# IN_V.net
KiCad netlist of a schematic drawn in Altium Designer
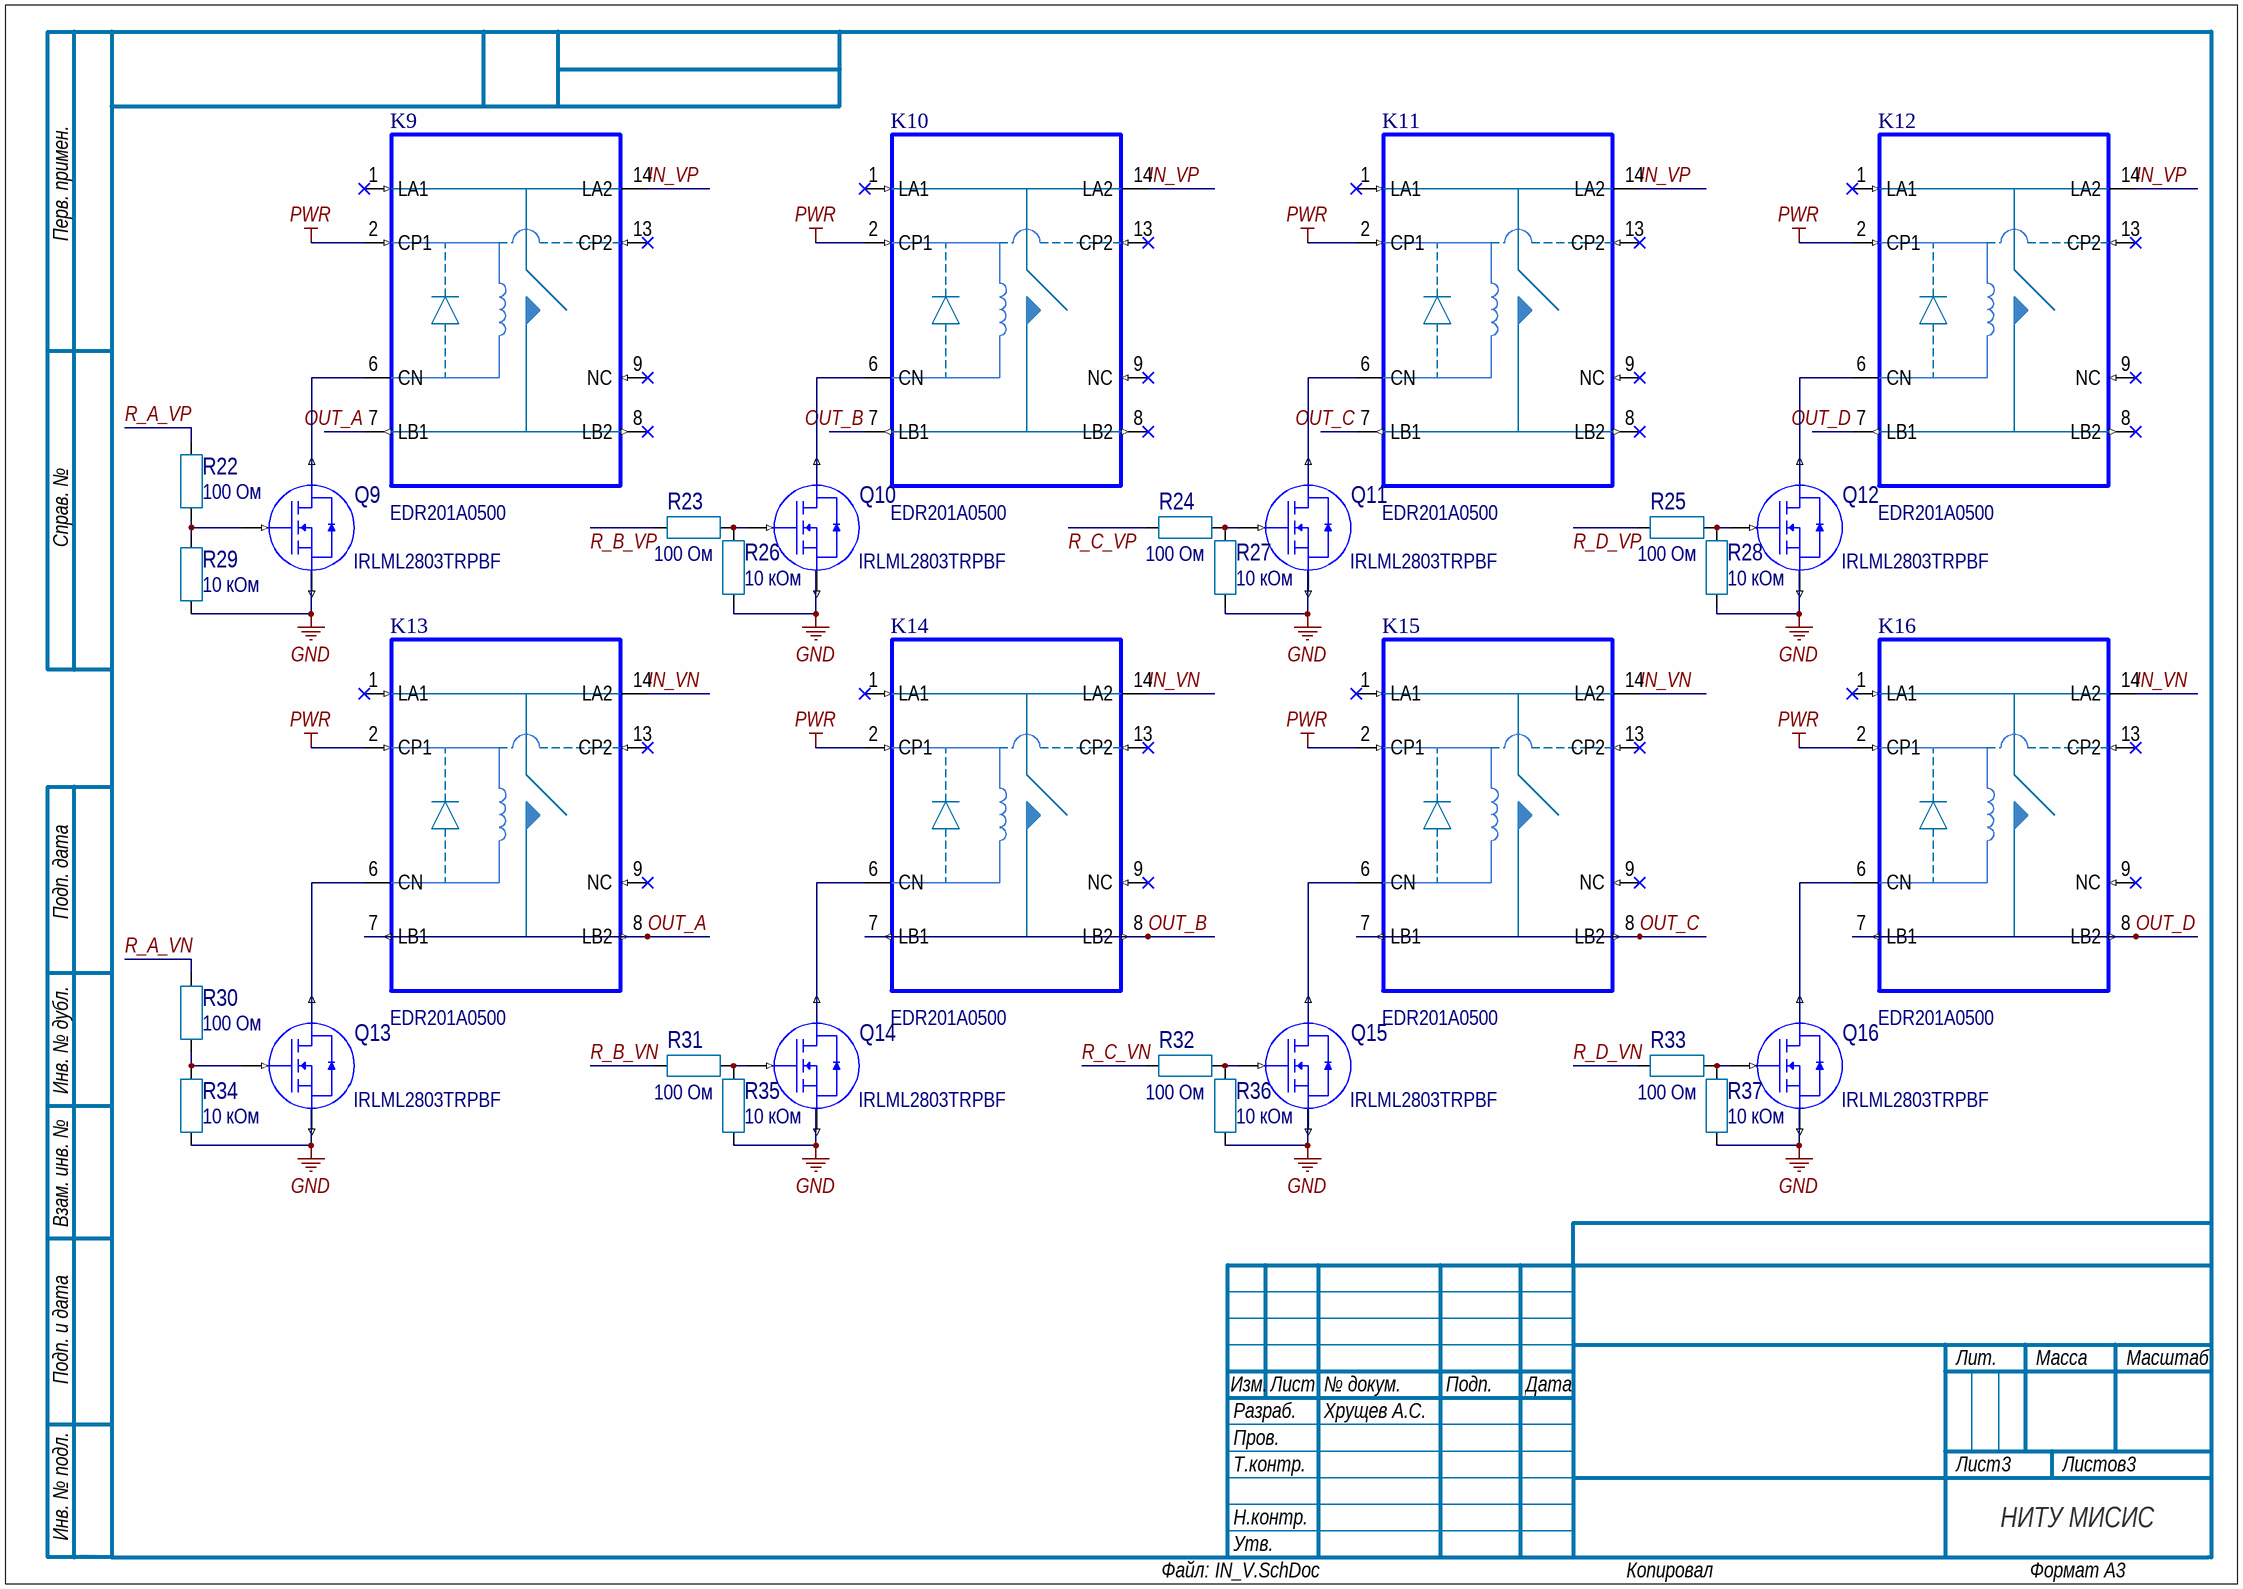
[diagram p0: IN_V.SchDoc]

(export (version "E")
  (design (tool "Eeschema 10.0.6"))
  (components
    (comp (ref "K9")
      (value "EDR201A0500")
      (footprint "DIP14")
      (description "Реле герконовое 5V / 1A,100V")
      (fields (field (name "MF") "Fairchild Semiconductor") (field (name "MP") "MM74HC32N"))
      (libsource (lib "EDR201A0500") (part "EDR201A0500"))
    )
    (comp (ref "K10")
      (value "EDR201A0500")
      (footprint "DIP14")
      (description "Реле герконовое 5V / 1A,100V")
      (fields (field (name "MF") "Fairchild Semiconductor") (field (name "MP") "MM74HC32N"))
      (libsource (lib "EDR201A0500") (part "EDR201A0500"))
    )
    (comp (ref "K11")
      (value "EDR201A0500")
      (footprint "DIP14")
      (description "Реле герконовое 5V / 1A,100V")
      (fields (field (name "MF") "Fairchild Semiconductor") (field (name "MP") "MM74HC32N"))
      (libsource (lib "EDR201A0500") (part "EDR201A0500"))
    )
    (comp (ref "K12")
      (value "EDR201A0500")
      (footprint "DIP14")
      (description "Реле герконовое 5V / 1A,100V")
      (fields (field (name "MF") "Fairchild Semiconductor") (field (name "MP") "MM74HC32N"))
      (libsource (lib "EDR201A0500") (part "EDR201A0500"))
    )
    (comp (ref "K13")
      (value "EDR201A0500")
      (footprint "DIP14")
      (description "Реле герконовое 5V / 1A,100V")
      (fields (field (name "MF") "Fairchild Semiconductor") (field (name "MP") "MM74HC32N"))
      (libsource (lib "EDR201A0500") (part "EDR201A0500"))
    )
    (comp (ref "K14")
      (value "EDR201A0500")
      (footprint "DIP14")
      (description "Реле герконовое 5V / 1A,100V")
      (fields (field (name "MF") "Fairchild Semiconductor") (field (name "MP") "MM74HC32N"))
      (libsource (lib "EDR201A0500") (part "EDR201A0500"))
    )
    (comp (ref "K15")
      (value "EDR201A0500")
      (footprint "DIP14")
      (description "Реле герконовое 5V / 1A,100V")
      (fields (field (name "MF") "Fairchild Semiconductor") (field (name "MP") "MM74HC32N"))
      (libsource (lib "EDR201A0500") (part "EDR201A0500"))
    )
    (comp (ref "K16")
      (value "EDR201A0500")
      (footprint "DIP14")
      (description "Реле герконовое 5V / 1A,100V")
      (fields (field (name "MF") "Fairchild Semiconductor") (field (name "MP") "MM74HC32N"))
      (libsource (lib "EDR201A0500") (part "EDR201A0500"))
    )
    (comp (ref "Q9")
      (value "IRLML2803TRPBF")
      (footprint "SOT23-3")
      (description "N-MOSFET 30V 1.2A SOT23")
      (libsource (lib "symbols") (part "IRLML2803TRPBF"))
    )
    (comp (ref "Q10")
      (value "IRLML2803TRPBF")
      (footprint "SOT23-3")
      (description "N-MOSFET 30V 1.2A SOT23")
      (libsource (lib "symbols") (part "IRLML2803TRPBF"))
    )
    (comp (ref "Q11")
      (value "IRLML2803TRPBF")
      (footprint "SOT23-3")
      (description "N-MOSFET 30V 1.2A SOT23")
      (libsource (lib "symbols") (part "IRLML2803TRPBF"))
    )
    (comp (ref "Q12")
      (value "IRLML2803TRPBF")
      (footprint "SOT23-3")
      (description "N-MOSFET 30V 1.2A SOT23")
      (libsource (lib "symbols") (part "IRLML2803TRPBF"))
    )
    (comp (ref "Q13")
      (value "IRLML2803TRPBF")
      (footprint "SOT23-3")
      (description "N-MOSFET 30V 1.2A SOT23")
      (libsource (lib "symbols") (part "IRLML2803TRPBF"))
    )
    (comp (ref "Q14")
      (value "IRLML2803TRPBF")
      (footprint "SOT23-3")
      (description "N-MOSFET 30V 1.2A SOT23")
      (libsource (lib "symbols") (part "IRLML2803TRPBF"))
    )
    (comp (ref "Q15")
      (value "IRLML2803TRPBF")
      (footprint "SOT23-3")
      (description "N-MOSFET 30V 1.2A SOT23")
      (libsource (lib "symbols") (part "IRLML2803TRPBF"))
    )
    (comp (ref "Q16")
      (value "IRLML2803TRPBF")
      (footprint "SOT23-3")
      (description "N-MOSFET 30V 1.2A SOT23")
      (libsource (lib "symbols") (part "IRLML2803TRPBF"))
    )
    (comp (ref "R22")
      (value "100 Ом")
      (footprint "R0805")
      (description "Резистор 100 Ом")
      (libsource (lib "GOST_2.728_Rezistory&Kondensatory") (part "R1_POSTOYANNYJ"))
    )
    (comp (ref "R23")
      (value "100 Ом")
      (footprint "R0805")
      (description "Резистор 100 Ом")
      (libsource (lib "") (part "R1_POSTOYANNYJ_1"))
    )
    (comp (ref "R24")
      (value "100 Ом")
      (footprint "R0805")
      (description "Резистор 100 Ом")
      (libsource (lib "") (part "R1_POSTOYANNYJ_1"))
    )
    (comp (ref "R25")
      (value "100 Ом")
      (footprint "R0805")
      (description "Резистор 100 Ом")
      (libsource (lib "") (part "R1_POSTOYANNYJ_1"))
    )
    (comp (ref "R26")
      (value "10 кОм")
      (footprint "R0805")
      (description "Резистор 100 Ом")
      (libsource (lib "GOST_2.728_Rezistory&Kondensatory") (part "R1_POSTOYANNYJ"))
    )
    (comp (ref "R27")
      (value "10 кОм")
      (footprint "R0805")
      (description "Резистор 100 Ом")
      (libsource (lib "GOST_2.728_Rezistory&Kondensatory") (part "R1_POSTOYANNYJ"))
    )
    (comp (ref "R28")
      (value "10 кОм")
      (footprint "R0805")
      (description "Резистор 100 Ом")
      (libsource (lib "GOST_2.728_Rezistory&Kondensatory") (part "R1_POSTOYANNYJ"))
    )
    (comp (ref "R29")
      (value "10 кОм")
      (footprint "R0805")
      (description "Резистор 100 Ом")
      (libsource (lib "GOST_2.728_Rezistory&Kondensatory") (part "R1_POSTOYANNYJ"))
    )
    (comp (ref "R30")
      (value "100 Ом")
      (footprint "R0805")
      (description "Резистор 100 Ом")
      (libsource (lib "GOST_2.728_Rezistory&Kondensatory") (part "R1_POSTOYANNYJ"))
    )
    (comp (ref "R31")
      (value "100 Ом")
      (footprint "R0805")
      (description "Резистор 100 Ом")
      (libsource (lib "") (part "R1_POSTOYANNYJ_1"))
    )
    (comp (ref "R32")
      (value "100 Ом")
      (footprint "R0805")
      (description "Резистор 100 Ом")
      (libsource (lib "") (part "R1_POSTOYANNYJ_1"))
    )
    (comp (ref "R33")
      (value "100 Ом")
      (footprint "R0805")
      (description "Резистор 100 Ом")
      (libsource (lib "") (part "R1_POSTOYANNYJ_1"))
    )
    (comp (ref "R34")
      (value "10 кОм")
      (footprint "R0805")
      (description "Резистор 100 Ом")
      (libsource (lib "GOST_2.728_Rezistory&Kondensatory") (part "R1_POSTOYANNYJ"))
    )
    (comp (ref "R35")
      (value "10 кОм")
      (footprint "R0805")
      (description "Резистор 100 Ом")
      (libsource (lib "GOST_2.728_Rezistory&Kondensatory") (part "R1_POSTOYANNYJ"))
    )
    (comp (ref "R36")
      (value "10 кОм")
      (footprint "R0805")
      (description "Резистор 100 Ом")
      (libsource (lib "GOST_2.728_Rezistory&Kondensatory") (part "R1_POSTOYANNYJ"))
    )
    (comp (ref "R37")
      (value "10 кОм")
      (footprint "R0805")
      (description "Резистор 100 Ом")
      (libsource (lib "GOST_2.728_Rezistory&Kondensatory") (part "R1_POSTOYANNYJ"))
    )
  )
  (nets
    (net (code "1") (name "/IN_VN") (class "Default")
      (node (ref "K13") (pin "14") (pinfunction "LA2_14") (pintype "power_in"))
      (node (ref "K14") (pin "14") (pinfunction "LA2_14") (pintype "power_in"))
      (node (ref "K15") (pin "14") (pinfunction "LA2_14") (pintype "power_in"))
      (node (ref "K16") (pin "14") (pinfunction "LA2_14") (pintype "power_in"))
    )
    (net (code "2") (name "/IN_VP") (class "Default")
      (node (ref "K10") (pin "14") (pinfunction "LA2_14") (pintype "power_in"))
      (node (ref "K11") (pin "14") (pinfunction "LA2_14") (pintype "power_in"))
      (node (ref "K12") (pin "14") (pinfunction "LA2_14") (pintype "power_in"))
      (node (ref "K9") (pin "14") (pinfunction "LA2_14") (pintype "power_in"))
    )
    (net (code "3") (name "/OUT_A") (class "Default")
      (node (ref "K13") (pin "7") (pinfunction "LB1_7") (pintype "output"))
      (node (ref "K13") (pin "8") (pinfunction "LB2_8") (pintype "output"))
      (node (ref "K9") (pin "7") (pinfunction "LB1_7") (pintype "output"))
    )
    (net (code "4") (name "/OUT_B") (class "Default")
      (node (ref "K10") (pin "7") (pinfunction "LB1_7") (pintype "output"))
      (node (ref "K14") (pin "7") (pinfunction "LB1_7") (pintype "output"))
      (node (ref "K14") (pin "8") (pinfunction "LB2_8") (pintype "output"))
    )
    (net (code "5") (name "/OUT_C") (class "Default")
      (node (ref "K11") (pin "7") (pinfunction "LB1_7") (pintype "output"))
      (node (ref "K15") (pin "7") (pinfunction "LB1_7") (pintype "output"))
      (node (ref "K15") (pin "8") (pinfunction "LB2_8") (pintype "output"))
    )
    (net (code "6") (name "/OUT_D") (class "Default")
      (node (ref "K12") (pin "7") (pinfunction "LB1_7") (pintype "output"))
      (node (ref "K16") (pin "7") (pinfunction "LB1_7") (pintype "output"))
      (node (ref "K16") (pin "8") (pinfunction "LB2_8") (pintype "output"))
    )
    (net (code "7") (name "/R_A_VN") (class "Default")
      (node (ref "R30") (pin "2") (pinfunction "2_2") (pintype "passive"))
    )
    (net (code "8") (name "/R_A_VP") (class "Default")
      (node (ref "R22") (pin "2") (pinfunction "2_2") (pintype "passive"))
    )
    (net (code "9") (name "/R_B_VN") (class "Default")
      (node (ref "R31") (pin "1") (pinfunction "1_1") (pintype "passive"))
    )
    (net (code "10") (name "/R_B_VP") (class "Default")
      (node (ref "R23") (pin "1") (pinfunction "1_1") (pintype "passive"))
    )
    (net (code "11") (name "/R_C_VN") (class "Default")
      (node (ref "R32") (pin "1") (pinfunction "1_1") (pintype "passive"))
    )
    (net (code "12") (name "/R_C_VP") (class "Default")
      (node (ref "R24") (pin "1") (pinfunction "1_1") (pintype "passive"))
    )
    (net (code "13") (name "/R_D_VN") (class "Default")
      (node (ref "R33") (pin "1") (pinfunction "1_1") (pintype "passive"))
    )
    (net (code "14") (name "/R_D_VP") (class "Default")
      (node (ref "R25") (pin "1") (pinfunction "1_1") (pintype "passive"))
    )
    (net (code "15") (name "GND") (class "Default")
      (node (ref "Q10") (pin "2") (pinfunction "S_2") (pintype "input"))
      (node (ref "Q11") (pin "2") (pinfunction "S_2") (pintype "input"))
      (node (ref "Q12") (pin "2") (pinfunction "S_2") (pintype "input"))
      (node (ref "Q13") (pin "2") (pinfunction "S_2") (pintype "input"))
      (node (ref "Q14") (pin "2") (pinfunction "S_2") (pintype "input"))
      (node (ref "Q15") (pin "2") (pinfunction "S_2") (pintype "input"))
      (node (ref "Q16") (pin "2") (pinfunction "S_2") (pintype "input"))
      (node (ref "Q9") (pin "2") (pinfunction "S_2") (pintype "input"))
      (node (ref "R26") (pin "1") (pinfunction "1_1") (pintype "passive"))
      (node (ref "R27") (pin "1") (pinfunction "1_1") (pintype "passive"))
      (node (ref "R28") (pin "1") (pinfunction "1_1") (pintype "passive"))
      (node (ref "R29") (pin "1") (pinfunction "1_1") (pintype "passive"))
      (node (ref "R34") (pin "1") (pinfunction "1_1") (pintype "passive"))
      (node (ref "R35") (pin "1") (pinfunction "1_1") (pintype "passive"))
      (node (ref "R36") (pin "1") (pinfunction "1_1") (pintype "passive"))
      (node (ref "R37") (pin "1") (pinfunction "1_1") (pintype "passive"))
    )
    (net (code "16") (name "Net-(K9-CN)") (class "Default")
      (node (ref "K9") (pin "6") (pinfunction "CN_6") (pintype "passive"))
      (node (ref "Q9") (pin "3") (pinfunction "D_3") (pintype "input"))
    )
    (net (code "17") (name "Net-(K10-CN)") (class "Default")
      (node (ref "K10") (pin "6") (pinfunction "CN_6") (pintype "passive"))
      (node (ref "Q10") (pin "3") (pinfunction "D_3") (pintype "input"))
    )
    (net (code "18") (name "Net-(K11-CN)") (class "Default")
      (node (ref "K11") (pin "6") (pinfunction "CN_6") (pintype "passive"))
      (node (ref "Q11") (pin "3") (pinfunction "D_3") (pintype "input"))
    )
    (net (code "19") (name "Net-(K12-CN)") (class "Default")
      (node (ref "K12") (pin "6") (pinfunction "CN_6") (pintype "passive"))
      (node (ref "Q12") (pin "3") (pinfunction "D_3") (pintype "input"))
    )
    (net (code "20") (name "Net-(K13-CN)") (class "Default")
      (node (ref "K13") (pin "6") (pinfunction "CN_6") (pintype "passive"))
      (node (ref "Q13") (pin "3") (pinfunction "D_3") (pintype "input"))
    )
    (net (code "21") (name "Net-(K14-CN)") (class "Default")
      (node (ref "K14") (pin "6") (pinfunction "CN_6") (pintype "passive"))
      (node (ref "Q14") (pin "3") (pinfunction "D_3") (pintype "input"))
    )
    (net (code "22") (name "Net-(K15-CN)") (class "Default")
      (node (ref "K15") (pin "6") (pinfunction "CN_6") (pintype "passive"))
      (node (ref "Q15") (pin "3") (pinfunction "D_3") (pintype "input"))
    )
    (net (code "23") (name "Net-(K16-CN)") (class "Default")
      (node (ref "K16") (pin "6") (pinfunction "CN_6") (pintype "passive"))
      (node (ref "Q16") (pin "3") (pinfunction "D_3") (pintype "input"))
    )
    (net (code "24") (name "Net-(Q9-G)") (class "Default")
      (node (ref "Q9") (pin "1") (pinfunction "G_1") (pintype "input"))
      (node (ref "R22") (pin "1") (pinfunction "1_1") (pintype "passive"))
      (node (ref "R29") (pin "2") (pinfunction "2_2") (pintype "passive"))
    )
    (net (code "25") (name "Net-(Q10-G)") (class "Default")
      (node (ref "Q10") (pin "1") (pinfunction "G_1") (pintype "input"))
      (node (ref "R23") (pin "2") (pinfunction "2_2") (pintype "passive"))
      (node (ref "R26") (pin "2") (pinfunction "2_2") (pintype "passive"))
    )
    (net (code "26") (name "Net-(Q11-G)") (class "Default")
      (node (ref "Q11") (pin "1") (pinfunction "G_1") (pintype "input"))
      (node (ref "R24") (pin "2") (pinfunction "2_2") (pintype "passive"))
      (node (ref "R27") (pin "2") (pinfunction "2_2") (pintype "passive"))
    )
    (net (code "27") (name "Net-(Q12-G)") (class "Default")
      (node (ref "Q12") (pin "1") (pinfunction "G_1") (pintype "input"))
      (node (ref "R25") (pin "2") (pinfunction "2_2") (pintype "passive"))
      (node (ref "R28") (pin "2") (pinfunction "2_2") (pintype "passive"))
    )
    (net (code "28") (name "Net-(Q13-G)") (class "Default")
      (node (ref "Q13") (pin "1") (pinfunction "G_1") (pintype "input"))
      (node (ref "R30") (pin "1") (pinfunction "1_1") (pintype "passive"))
      (node (ref "R34") (pin "2") (pinfunction "2_2") (pintype "passive"))
    )
    (net (code "29") (name "Net-(Q14-G)") (class "Default")
      (node (ref "Q14") (pin "1") (pinfunction "G_1") (pintype "input"))
      (node (ref "R31") (pin "2") (pinfunction "2_2") (pintype "passive"))
      (node (ref "R35") (pin "2") (pinfunction "2_2") (pintype "passive"))
    )
    (net (code "30") (name "Net-(Q15-G)") (class "Default")
      (node (ref "Q15") (pin "1") (pinfunction "G_1") (pintype "input"))
      (node (ref "R32") (pin "2") (pinfunction "2_2") (pintype "passive"))
      (node (ref "R36") (pin "2") (pinfunction "2_2") (pintype "passive"))
    )
    (net (code "31") (name "Net-(Q16-G)") (class "Default")
      (node (ref "Q16") (pin "1") (pinfunction "G_1") (pintype "input"))
      (node (ref "R33") (pin "2") (pinfunction "2_2") (pintype "passive"))
      (node (ref "R37") (pin "2") (pinfunction "2_2") (pintype "passive"))
    )
    (net (code "32") (name "PWR") (class "Default")
      (node (ref "K10") (pin "2") (pinfunction "CP1_2") (pintype "input"))
      (node (ref "K11") (pin "2") (pinfunction "CP1_2") (pintype "input"))
      (node (ref "K12") (pin "2") (pinfunction "CP1_2") (pintype "input"))
      (node (ref "K13") (pin "2") (pinfunction "CP1_2") (pintype "input"))
      (node (ref "K14") (pin "2") (pinfunction "CP1_2") (pintype "input"))
      (node (ref "K15") (pin "2") (pinfunction "CP1_2") (pintype "input"))
      (node (ref "K16") (pin "2") (pinfunction "CP1_2") (pintype "input"))
      (node (ref "K9") (pin "2") (pinfunction "CP1_2") (pintype "input"))
    )
    (net (code "33") (name "unconnected-(K9-CP2-Pad13)") (class "Default")
      (node (ref "K9") (pin "13") (pinfunction "CP2_13") (pintype "input+no_connect"))
    )
    (net (code "34") (name "unconnected-(K9-LA1-Pad1)") (class "Default")
      (node (ref "K9") (pin "1") (pinfunction "LA1_1") (pintype "input+no_connect"))
    )
    (net (code "35") (name "unconnected-(K9-LB2-Pad8)") (class "Default")
      (node (ref "K9") (pin "8") (pinfunction "LB2_8") (pintype "output+no_connect"))
    )
    (net (code "36") (name "unconnected-(K9-NC-Pad9)") (class "Default")
      (node (ref "K9") (pin "9") (pinfunction "NC_9") (pintype "input+no_connect"))
    )
    (net (code "37") (name "unconnected-(K10-CP2-Pad13)") (class "Default")
      (node (ref "K10") (pin "13") (pinfunction "CP2_13") (pintype "input+no_connect"))
    )
    (net (code "38") (name "unconnected-(K10-LA1-Pad1)") (class "Default")
      (node (ref "K10") (pin "1") (pinfunction "LA1_1") (pintype "input+no_connect"))
    )
    (net (code "39") (name "unconnected-(K10-LB2-Pad8)") (class "Default")
      (node (ref "K10") (pin "8") (pinfunction "LB2_8") (pintype "output+no_connect"))
    )
    (net (code "40") (name "unconnected-(K10-NC-Pad9)") (class "Default")
      (node (ref "K10") (pin "9") (pinfunction "NC_9") (pintype "input+no_connect"))
    )
    (net (code "41") (name "unconnected-(K11-CP2-Pad13)") (class "Default")
      (node (ref "K11") (pin "13") (pinfunction "CP2_13") (pintype "input+no_connect"))
    )
    (net (code "42") (name "unconnected-(K11-LA1-Pad1)") (class "Default")
      (node (ref "K11") (pin "1") (pinfunction "LA1_1") (pintype "input+no_connect"))
    )
    (net (code "43") (name "unconnected-(K11-LB2-Pad8)") (class "Default")
      (node (ref "K11") (pin "8") (pinfunction "LB2_8") (pintype "output+no_connect"))
    )
    (net (code "44") (name "unconnected-(K11-NC-Pad9)") (class "Default")
      (node (ref "K11") (pin "9") (pinfunction "NC_9") (pintype "input+no_connect"))
    )
    (net (code "45") (name "unconnected-(K12-CP2-Pad13)") (class "Default")
      (node (ref "K12") (pin "13") (pinfunction "CP2_13") (pintype "input+no_connect"))
    )
    (net (code "46") (name "unconnected-(K12-LA1-Pad1)") (class "Default")
      (node (ref "K12") (pin "1") (pinfunction "LA1_1") (pintype "input+no_connect"))
    )
    (net (code "47") (name "unconnected-(K12-LB2-Pad8)") (class "Default")
      (node (ref "K12") (pin "8") (pinfunction "LB2_8") (pintype "output+no_connect"))
    )
    (net (code "48") (name "unconnected-(K12-NC-Pad9)") (class "Default")
      (node (ref "K12") (pin "9") (pinfunction "NC_9") (pintype "input+no_connect"))
    )
    (net (code "49") (name "unconnected-(K13-CP2-Pad13)") (class "Default")
      (node (ref "K13") (pin "13") (pinfunction "CP2_13") (pintype "input+no_connect"))
    )
    (net (code "50") (name "unconnected-(K13-LA1-Pad1)") (class "Default")
      (node (ref "K13") (pin "1") (pinfunction "LA1_1") (pintype "input+no_connect"))
    )
    (net (code "51") (name "unconnected-(K13-NC-Pad9)") (class "Default")
      (node (ref "K13") (pin "9") (pinfunction "NC_9") (pintype "input+no_connect"))
    )
    (net (code "52") (name "unconnected-(K14-CP2-Pad13)") (class "Default")
      (node (ref "K14") (pin "13") (pinfunction "CP2_13") (pintype "input+no_connect"))
    )
    (net (code "53") (name "unconnected-(K14-LA1-Pad1)") (class "Default")
      (node (ref "K14") (pin "1") (pinfunction "LA1_1") (pintype "input+no_connect"))
    )
    (net (code "54") (name "unconnected-(K14-NC-Pad9)") (class "Default")
      (node (ref "K14") (pin "9") (pinfunction "NC_9") (pintype "input+no_connect"))
    )
    (net (code "55") (name "unconnected-(K15-CP2-Pad13)") (class "Default")
      (node (ref "K15") (pin "13") (pinfunction "CP2_13") (pintype "input+no_connect"))
    )
    (net (code "56") (name "unconnected-(K15-LA1-Pad1)") (class "Default")
      (node (ref "K15") (pin "1") (pinfunction "LA1_1") (pintype "input+no_connect"))
    )
    (net (code "57") (name "unconnected-(K15-NC-Pad9)") (class "Default")
      (node (ref "K15") (pin "9") (pinfunction "NC_9") (pintype "input+no_connect"))
    )
    (net (code "58") (name "unconnected-(K16-CP2-Pad13)") (class "Default")
      (node (ref "K16") (pin "13") (pinfunction "CP2_13") (pintype "input+no_connect"))
    )
    (net (code "59") (name "unconnected-(K16-LA1-Pad1)") (class "Default")
      (node (ref "K16") (pin "1") (pinfunction "LA1_1") (pintype "input+no_connect"))
    )
    (net (code "60") (name "unconnected-(K16-NC-Pad9)") (class "Default")
      (node (ref "K16") (pin "9") (pinfunction "NC_9") (pintype "input+no_connect"))
    )
  )
)
